# DESIGN7IH.net
KiCad netlist of a schematic drawn in EAGLE
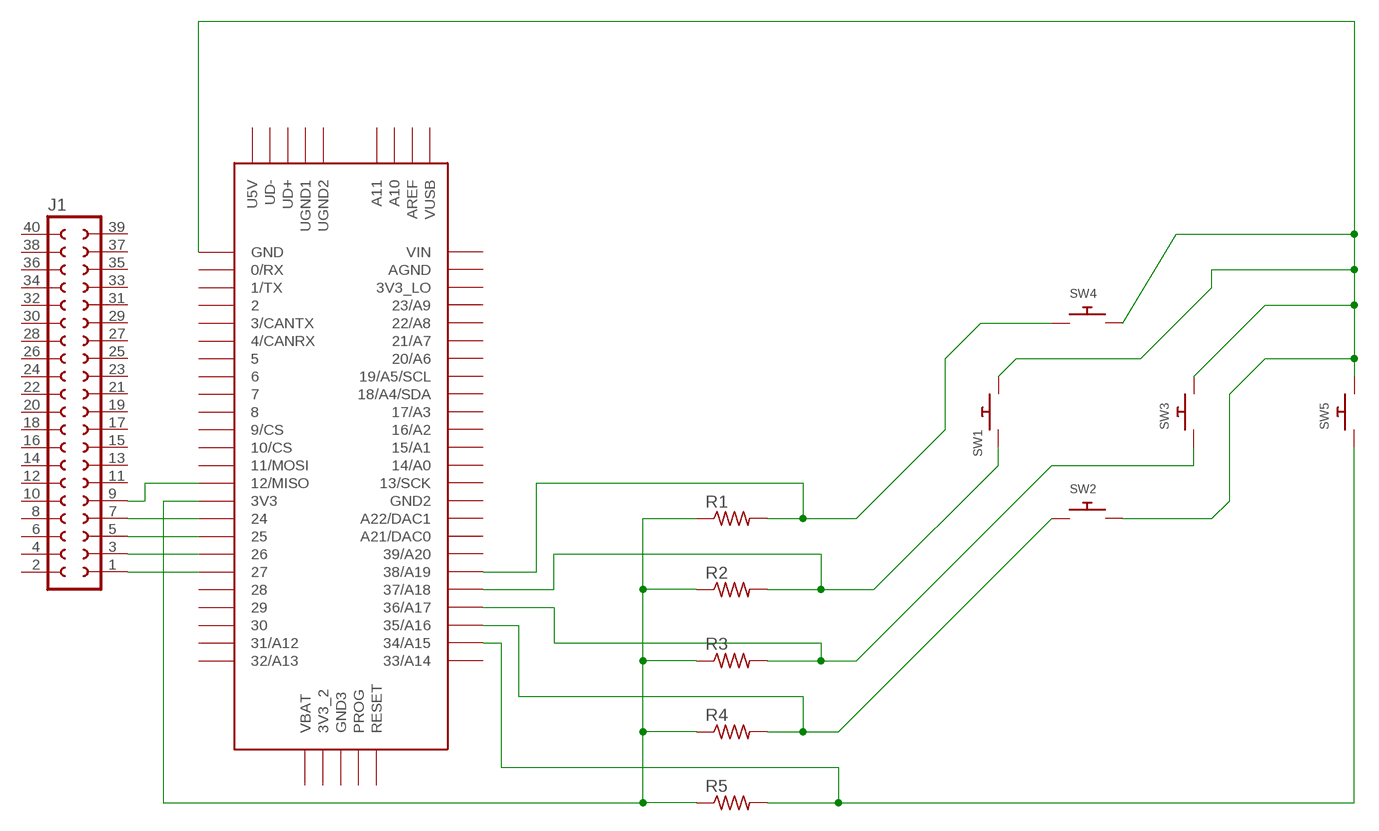
[diagram p0: schematic, sheet 1]

(export (version "E")
  (design (tool "Eeschema 10.0.6"))
  (components
    (comp (ref "J1")
      (value "SOCKET-40V")
      (footprint "eagle-import:S40V")
      (libsource (lib "eagle-import") (part "SOCKET-40V"))
    )
    (comp (ref "R1")
      (value "R-US_0204/5")
      (footprint "eagle-import:0204_5")
      (libsource (lib "eagle-import") (part "R-US_0204/5"))
    )
    (comp (ref "R2")
      (value "R-US_0204/5")
      (footprint "eagle-import:0204_5")
      (libsource (lib "eagle-import") (part "R-US_0204/5"))
    )
    (comp (ref "R3")
      (value "R-US_0204/5")
      (footprint "eagle-import:0204_5")
      (libsource (lib "eagle-import") (part "R-US_0204/5"))
    )
    (comp (ref "R4")
      (value "R-US_0204/5")
      (footprint "eagle-import:0204_5")
      (libsource (lib "eagle-import") (part "R-US_0204/5"))
    )
    (comp (ref "R5")
      (value "R-US_0204/5")
      (footprint "eagle-import:0204_5")
      (libsource (lib "eagle-import") (part "R-US_0204/5"))
    )
    (comp (ref "SW1")
      (value "SWITCH_PUSHBUTTONEVQ-PE")
      (footprint "eagle-import:TACT_PANA-EVQ")
      (libsource (lib "eagle-import") (part "SWITCH_PUSHBUTTONEVQ-PE"))
    )
    (comp (ref "SW2")
      (value "SWITCH_PUSHBUTTONEVQ-PE")
      (footprint "eagle-import:TACT_PANA-EVQ")
      (libsource (lib "eagle-import") (part "SWITCH_PUSHBUTTONEVQ-PE"))
    )
    (comp (ref "SW3")
      (value "SWITCH_PUSHBUTTONEVQ-PE")
      (footprint "eagle-import:TACT_PANA-EVQ")
      (libsource (lib "eagle-import") (part "SWITCH_PUSHBUTTONEVQ-PE"))
    )
    (comp (ref "SW4")
      (value "SWITCH_PUSHBUTTONEVQ-PE")
      (footprint "eagle-import:TACT_PANA-EVQ")
      (libsource (lib "eagle-import") (part "SWITCH_PUSHBUTTONEVQ-PE"))
    )
    (comp (ref "SW5")
      (value "SWITCH_PUSHBUTTONEVQ-PE")
      (footprint "eagle-import:TACT_PANA-EVQ")
      (libsource (lib "eagle-import") (part "SWITCH_PUSHBUTTONEVQ-PE"))
    )
    (comp (ref "U$1")
      (value "TEENSY_3.5/3.6")
      (footprint "eagle-import:TEENSY_3.5_3.6")
      (libsource (lib "eagle-import") (part "TEENSY_3.5/3.6"))
    )
  )
  (nets
    (net (code "1") (name "Net-(J1-Pad1)") (class "Default")
      (node (ref "J1") (pin "1") (pinfunction "1_1") (pintype "passive"))
      (node (ref "U$1") (pin "27") (pinfunction "27_27") (pintype "bidirectional"))
    )
    (net (code "2") (name "Net-(J1-Pad3)") (class "Default")
      (node (ref "J1") (pin "3") (pinfunction "3_3") (pintype "passive"))
      (node (ref "U$1") (pin "26") (pinfunction "26_26") (pintype "bidirectional"))
    )
    (net (code "3") (name "Net-(J1-Pad5)") (class "Default")
      (node (ref "J1") (pin "5") (pinfunction "5_5") (pintype "passive"))
      (node (ref "U$1") (pin "25") (pinfunction "25_25") (pintype "bidirectional"))
    )
    (net (code "4") (name "Net-(J1-Pad7)") (class "Default")
      (node (ref "J1") (pin "7") (pinfunction "7_7") (pintype "passive"))
      (node (ref "U$1") (pin "24") (pinfunction "24_24") (pintype "bidirectional"))
    )
    (net (code "5") (name "Net-(J1-Pad9)") (class "Default")
      (node (ref "J1") (pin "9") (pinfunction "9_9") (pintype "passive"))
      (node (ref "U$1") (pin "12/MISO") (pinfunction "12/MISO_12/MISO") (pintype "bidirectional"))
    )
    (net (code "6") (name "Net-(R1-Pad1)") (class "Default")
      (node (ref "R1") (pin "1") (pinfunction "1_1") (pintype "passive"))
      (node (ref "R2") (pin "1") (pinfunction "1_1") (pintype "passive"))
      (node (ref "R3") (pin "1") (pinfunction "1_1") (pintype "passive"))
      (node (ref "R4") (pin "1") (pinfunction "1_1") (pintype "passive"))
      (node (ref "R5") (pin "1") (pinfunction "1_1") (pintype "passive"))
      (node (ref "U$1") (pin "3V3") (pinfunction "3V3_3V3") (pintype "bidirectional"))
    )
    (net (code "7") (name "Net-(R1-Pad2)") (class "Default")
      (node (ref "R1") (pin "2") (pinfunction "2_2") (pintype "passive"))
      (node (ref "SW4") (pin "P$1") (pinfunction "P$1_P$1") (pintype "passive"))
      (node (ref "U$1") (pin "38/A19") (pinfunction "38/A19_38/A19") (pintype "bidirectional"))
    )
    (net (code "8") (name "Net-(R2-Pad2)") (class "Default")
      (node (ref "R2") (pin "2") (pinfunction "2_2") (pintype "passive"))
      (node (ref "SW1") (pin "P$1") (pinfunction "P$1_P$1") (pintype "passive"))
      (node (ref "U$1") (pin "37/A18") (pinfunction "37/A18_37/A18") (pintype "bidirectional"))
    )
    (net (code "9") (name "Net-(R3-Pad2)") (class "Default")
      (node (ref "R3") (pin "2") (pinfunction "2_2") (pintype "passive"))
      (node (ref "SW3") (pin "P$1") (pinfunction "P$1_P$1") (pintype "passive"))
      (node (ref "U$1") (pin "36/A17") (pinfunction "36/A17_36/A17") (pintype "bidirectional"))
    )
    (net (code "10") (name "Net-(R4-Pad2)") (class "Default")
      (node (ref "R4") (pin "2") (pinfunction "2_2") (pintype "passive"))
      (node (ref "SW2") (pin "P$1") (pinfunction "P$1_P$1") (pintype "passive"))
      (node (ref "U$1") (pin "35/A16") (pinfunction "35/A16_35/A16") (pintype "bidirectional"))
    )
    (net (code "11") (name "Net-(R5-Pad2)") (class "Default")
      (node (ref "R5") (pin "2") (pinfunction "2_2") (pintype "passive"))
      (node (ref "SW5") (pin "P$1") (pinfunction "P$1_P$1") (pintype "passive"))
      (node (ref "U$1") (pin "34/A15") (pinfunction "34/A15_34/A15") (pintype "bidirectional"))
    )
    (net (code "12") (name "Net-(SW1-PadP$2)") (class "Default")
      (node (ref "SW1") (pin "P$2") (pinfunction "P$2_P$2") (pintype "passive"))
      (node (ref "SW2") (pin "P$2") (pinfunction "P$2_P$2") (pintype "passive"))
      (node (ref "SW3") (pin "P$2") (pinfunction "P$2_P$2") (pintype "passive"))
      (node (ref "SW4") (pin "P$2") (pinfunction "P$2_P$2") (pintype "passive"))
      (node (ref "SW5") (pin "P$2") (pinfunction "P$2_P$2") (pintype "passive"))
      (node (ref "U$1") (pin "GND") (pinfunction "GND_GND") (pintype "bidirectional"))
    )
    (net (code "13") (name "unconnected-(J1-Pad2)") (class "Default")
      (node (ref "J1") (pin "2") (pinfunction "2_2") (pintype "passive"))
    )
    (net (code "14") (name "unconnected-(J1-Pad4)") (class "Default")
      (node (ref "J1") (pin "4") (pinfunction "4_4") (pintype "passive"))
    )
    (net (code "15") (name "unconnected-(J1-Pad6)") (class "Default")
      (node (ref "J1") (pin "6") (pinfunction "6_6") (pintype "passive"))
    )
    (net (code "16") (name "unconnected-(J1-Pad8)") (class "Default")
      (node (ref "J1") (pin "8") (pinfunction "8_8") (pintype "passive"))
    )
    (net (code "17") (name "unconnected-(J1-Pad10)") (class "Default")
      (node (ref "J1") (pin "10") (pinfunction "10_10") (pintype "passive"))
    )
    (net (code "18") (name "unconnected-(J1-Pad11)") (class "Default")
      (node (ref "J1") (pin "11") (pinfunction "11_11") (pintype "passive"))
    )
    (net (code "19") (name "unconnected-(J1-Pad12)") (class "Default")
      (node (ref "J1") (pin "12") (pinfunction "12_12") (pintype "passive"))
    )
    (net (code "20") (name "unconnected-(J1-Pad13)") (class "Default")
      (node (ref "J1") (pin "13") (pinfunction "13_13") (pintype "passive"))
    )
    (net (code "21") (name "unconnected-(J1-Pad14)") (class "Default")
      (node (ref "J1") (pin "14") (pinfunction "14_14") (pintype "passive"))
    )
    (net (code "22") (name "unconnected-(J1-Pad15)") (class "Default")
      (node (ref "J1") (pin "15") (pinfunction "15_15") (pintype "passive"))
    )
    (net (code "23") (name "unconnected-(J1-Pad16)") (class "Default")
      (node (ref "J1") (pin "16") (pinfunction "16_16") (pintype "passive"))
    )
    (net (code "24") (name "unconnected-(J1-Pad17)") (class "Default")
      (node (ref "J1") (pin "17") (pinfunction "17_17") (pintype "passive"))
    )
    (net (code "25") (name "unconnected-(J1-Pad18)") (class "Default")
      (node (ref "J1") (pin "18") (pinfunction "18_18") (pintype "passive"))
    )
    (net (code "26") (name "unconnected-(J1-Pad19)") (class "Default")
      (node (ref "J1") (pin "19") (pinfunction "19_19") (pintype "passive"))
    )
    (net (code "27") (name "unconnected-(J1-Pad20)") (class "Default")
      (node (ref "J1") (pin "20") (pinfunction "20_20") (pintype "passive"))
    )
    (net (code "28") (name "unconnected-(J1-Pad21)") (class "Default")
      (node (ref "J1") (pin "21") (pinfunction "21_21") (pintype "passive"))
    )
    (net (code "29") (name "unconnected-(J1-Pad22)") (class "Default")
      (node (ref "J1") (pin "22") (pinfunction "22_22") (pintype "passive"))
    )
    (net (code "30") (name "unconnected-(J1-Pad23)") (class "Default")
      (node (ref "J1") (pin "23") (pinfunction "23_23") (pintype "passive"))
    )
    (net (code "31") (name "unconnected-(J1-Pad24)") (class "Default")
      (node (ref "J1") (pin "24") (pinfunction "24_24") (pintype "passive"))
    )
    (net (code "32") (name "unconnected-(J1-Pad25)") (class "Default")
      (node (ref "J1") (pin "25") (pinfunction "25_25") (pintype "passive"))
    )
    (net (code "33") (name "unconnected-(J1-Pad26)") (class "Default")
      (node (ref "J1") (pin "26") (pinfunction "26_26") (pintype "passive"))
    )
    (net (code "34") (name "unconnected-(J1-Pad27)") (class "Default")
      (node (ref "J1") (pin "27") (pinfunction "27_27") (pintype "passive"))
    )
    (net (code "35") (name "unconnected-(J1-Pad28)") (class "Default")
      (node (ref "J1") (pin "28") (pinfunction "28_28") (pintype "passive"))
    )
    (net (code "36") (name "unconnected-(J1-Pad29)") (class "Default")
      (node (ref "J1") (pin "29") (pinfunction "29_29") (pintype "passive"))
    )
    (net (code "37") (name "unconnected-(J1-Pad30)") (class "Default")
      (node (ref "J1") (pin "30") (pinfunction "30_30") (pintype "passive"))
    )
    (net (code "38") (name "unconnected-(J1-Pad31)") (class "Default")
      (node (ref "J1") (pin "31") (pinfunction "31_31") (pintype "passive"))
    )
    (net (code "39") (name "unconnected-(J1-Pad32)") (class "Default")
      (node (ref "J1") (pin "32") (pinfunction "32_32") (pintype "passive"))
    )
    (net (code "40") (name "unconnected-(J1-Pad33)") (class "Default")
      (node (ref "J1") (pin "33") (pinfunction "33_33") (pintype "passive"))
    )
    (net (code "41") (name "unconnected-(J1-Pad34)") (class "Default")
      (node (ref "J1") (pin "34") (pinfunction "34_34") (pintype "passive"))
    )
    (net (code "42") (name "unconnected-(J1-Pad35)") (class "Default")
      (node (ref "J1") (pin "35") (pinfunction "35_35") (pintype "passive"))
    )
    (net (code "43") (name "unconnected-(J1-Pad36)") (class "Default")
      (node (ref "J1") (pin "36") (pinfunction "36_36") (pintype "passive"))
    )
    (net (code "44") (name "unconnected-(J1-Pad37)") (class "Default")
      (node (ref "J1") (pin "37") (pinfunction "37_37") (pintype "passive"))
    )
    (net (code "45") (name "unconnected-(J1-Pad38)") (class "Default")
      (node (ref "J1") (pin "38") (pinfunction "38_38") (pintype "passive"))
    )
    (net (code "46") (name "unconnected-(J1-Pad39)") (class "Default")
      (node (ref "J1") (pin "39") (pinfunction "39_39") (pintype "passive"))
    )
    (net (code "47") (name "unconnected-(J1-Pad40)") (class "Default")
      (node (ref "J1") (pin "40") (pinfunction "40_40") (pintype "passive"))
    )
    (net (code "48") (name "unconnected-(U$1-A21{slash}DAC0-Pad21{slash}DAC0)") (class "Default")
      (node (ref "U$1") (pin "21/DAC0") (pinfunction "A21/DAC0_21/DAC0") (pintype "bidirectional"))
    )
    (net (code "49") (name "unconnected-(U$1-Pad0{slash}RX)") (class "Default")
      (node (ref "U$1") (pin "0/RX") (pinfunction "0/RX_0/RX") (pintype "bidirectional"))
    )
    (net (code "50") (name "unconnected-(U$1-Pad1{slash}TX)") (class "Default")
      (node (ref "U$1") (pin "1/TX") (pinfunction "1/TX_1/TX") (pintype "bidirectional"))
    )
    (net (code "51") (name "unconnected-(U$1-Pad2)") (class "Default")
      (node (ref "U$1") (pin "2") (pinfunction "2_2") (pintype "bidirectional"))
    )
    (net (code "52") (name "unconnected-(U$1-Pad3V3_2)") (class "Default")
      (node (ref "U$1") (pin "3V3_2") (pinfunction "3V3_2_3V3_2") (pintype "bidirectional"))
    )
    (net (code "53") (name "unconnected-(U$1-Pad3V3_LO)") (class "Default")
      (node (ref "U$1") (pin "3V3_LO") (pinfunction "3V3_LO_3V3_LO") (pintype "bidirectional"))
    )
    (net (code "54") (name "unconnected-(U$1-Pad3{slash}CANTX)") (class "Default")
      (node (ref "U$1") (pin "3/CANTX") (pinfunction "3/CANTX_3/CANTX") (pintype "bidirectional"))
    )
    (net (code "55") (name "unconnected-(U$1-Pad4{slash}CANRX)") (class "Default")
      (node (ref "U$1") (pin "4/CANRX") (pinfunction "4/CANRX_4/CANRX") (pintype "bidirectional"))
    )
    (net (code "56") (name "unconnected-(U$1-Pad5)") (class "Default")
      (node (ref "U$1") (pin "5") (pinfunction "5_5") (pintype "bidirectional"))
    )
    (net (code "57") (name "unconnected-(U$1-Pad6)") (class "Default")
      (node (ref "U$1") (pin "6") (pinfunction "6_6") (pintype "bidirectional"))
    )
    (net (code "58") (name "unconnected-(U$1-Pad7)") (class "Default")
      (node (ref "U$1") (pin "7") (pinfunction "7_7") (pintype "bidirectional"))
    )
    (net (code "59") (name "unconnected-(U$1-Pad8)") (class "Default")
      (node (ref "U$1") (pin "8") (pinfunction "8_8") (pintype "bidirectional"))
    )
    (net (code "60") (name "unconnected-(U$1-Pad9{slash}CS)") (class "Default")
      (node (ref "U$1") (pin "9/CS") (pinfunction "9/CS_9/CS") (pintype "bidirectional"))
    )
    (net (code "61") (name "unconnected-(U$1-Pad10{slash}CS)") (class "Default")
      (node (ref "U$1") (pin "10/CS") (pinfunction "10/CS_10/CS") (pintype "bidirectional"))
    )
    (net (code "62") (name "unconnected-(U$1-Pad11{slash}MOSI)") (class "Default")
      (node (ref "U$1") (pin "11/MOSI") (pinfunction "11/MOSI_11/MOSI") (pintype "bidirectional"))
    )
    (net (code "63") (name "unconnected-(U$1-Pad13{slash}SCK)") (class "Default")
      (node (ref "U$1") (pin "13/SCK") (pinfunction "13/SCK_13/SCK") (pintype "bidirectional"))
    )
    (net (code "64") (name "unconnected-(U$1-Pad14{slash}A0)") (class "Default")
      (node (ref "U$1") (pin "14/A0") (pinfunction "14/A0_14/A0") (pintype "bidirectional"))
    )
    (net (code "65") (name "unconnected-(U$1-Pad15{slash}A1)") (class "Default")
      (node (ref "U$1") (pin "15/A1") (pinfunction "15/A1_15/A1") (pintype "bidirectional"))
    )
    (net (code "66") (name "unconnected-(U$1-Pad16{slash}A2)") (class "Default")
      (node (ref "U$1") (pin "16/A2") (pinfunction "16/A2_16/A2") (pintype "bidirectional"))
    )
    (net (code "67") (name "unconnected-(U$1-Pad17{slash}A3)") (class "Default")
      (node (ref "U$1") (pin "17/A3") (pinfunction "17/A3_17/A3") (pintype "bidirectional"))
    )
    (net (code "68") (name "unconnected-(U$1-Pad18{slash}A4{slash}SDA)") (class "Default")
      (node (ref "U$1") (pin "18/A4/SDA") (pinfunction "18/A4/SDA_18/A4/SDA") (pintype "bidirectional"))
    )
    (net (code "69") (name "unconnected-(U$1-Pad19{slash}A5{slash}SCL)") (class "Default")
      (node (ref "U$1") (pin "19/A5/SCL") (pinfunction "19/A5/SCL_19/A5/SCL") (pintype "bidirectional"))
    )
    (net (code "70") (name "unconnected-(U$1-Pad20{slash}A6)") (class "Default")
      (node (ref "U$1") (pin "20/A6") (pinfunction "20/A6_20/A6") (pintype "bidirectional"))
    )
    (net (code "71") (name "unconnected-(U$1-Pad21{slash}A7)") (class "Default")
      (node (ref "U$1") (pin "21/A7") (pinfunction "21/A7_21/A7") (pintype "bidirectional"))
    )
    (net (code "72") (name "unconnected-(U$1-Pad22{slash}A8)") (class "Default")
      (node (ref "U$1") (pin "22/A8") (pinfunction "22/A8_22/A8") (pintype "bidirectional"))
    )
    (net (code "73") (name "unconnected-(U$1-Pad23{slash}A9)") (class "Default")
      (node (ref "U$1") (pin "23/A9") (pinfunction "23/A9_23/A9") (pintype "bidirectional"))
    )
    (net (code "74") (name "unconnected-(U$1-Pad28)") (class "Default")
      (node (ref "U$1") (pin "28") (pinfunction "28_28") (pintype "bidirectional"))
    )
    (net (code "75") (name "unconnected-(U$1-Pad29)") (class "Default")
      (node (ref "U$1") (pin "29") (pinfunction "29_29") (pintype "bidirectional"))
    )
    (net (code "76") (name "unconnected-(U$1-Pad30)") (class "Default")
      (node (ref "U$1") (pin "30") (pinfunction "30_30") (pintype "bidirectional"))
    )
    (net (code "77") (name "unconnected-(U$1-Pad31{slash}A12)") (class "Default")
      (node (ref "U$1") (pin "31/A12") (pinfunction "31/A12_31/A12") (pintype "bidirectional"))
    )
    (net (code "78") (name "unconnected-(U$1-Pad32{slash}A13)") (class "Default")
      (node (ref "U$1") (pin "32/A13") (pinfunction "32/A13_32/A13") (pintype "bidirectional"))
    )
    (net (code "79") (name "unconnected-(U$1-Pad33{slash}A14)") (class "Default")
      (node (ref "U$1") (pin "33/A14") (pinfunction "33/A14_33/A14") (pintype "bidirectional"))
    )
    (net (code "80") (name "unconnected-(U$1-Pad39{slash}A20)") (class "Default")
      (node (ref "U$1") (pin "39/A20") (pinfunction "39/A20_39/A20") (pintype "bidirectional"))
    )
    (net (code "81") (name "unconnected-(U$1-PadA10)") (class "Default")
      (node (ref "U$1") (pin "A10") (pinfunction "A10_A10") (pintype "bidirectional"))
    )
    (net (code "82") (name "unconnected-(U$1-PadA11)") (class "Default")
      (node (ref "U$1") (pin "A11") (pinfunction "A11_A11") (pintype "bidirectional"))
    )
    (net (code "83") (name "unconnected-(U$1-PadA22{slash}DAC1)") (class "Default")
      (node (ref "U$1") (pin "A22/DAC1") (pinfunction "A22/DAC1_A22/DAC1") (pintype "bidirectional"))
    )
    (net (code "84") (name "unconnected-(U$1-PadAGND)") (class "Default")
      (node (ref "U$1") (pin "AGND") (pinfunction "AGND_AGND") (pintype "bidirectional"))
    )
    (net (code "85") (name "unconnected-(U$1-PadAREF)") (class "Default")
      (node (ref "U$1") (pin "AREF") (pinfunction "AREF_AREF") (pintype "bidirectional"))
    )
    (net (code "86") (name "unconnected-(U$1-PadGND2)") (class "Default")
      (node (ref "U$1") (pin "GND2") (pinfunction "GND2_GND2") (pintype "bidirectional"))
    )
    (net (code "87") (name "unconnected-(U$1-PadGND3)") (class "Default")
      (node (ref "U$1") (pin "GND3") (pinfunction "GND3_GND3") (pintype "bidirectional"))
    )
    (net (code "88") (name "unconnected-(U$1-PadPROG)") (class "Default")
      (node (ref "U$1") (pin "PROG") (pinfunction "PROG_PROG") (pintype "bidirectional"))
    )
    (net (code "89") (name "unconnected-(U$1-PadRESET)") (class "Default")
      (node (ref "U$1") (pin "RESET") (pinfunction "RESET_RESET") (pintype "bidirectional"))
    )
    (net (code "90") (name "unconnected-(U$1-PadU5V)") (class "Default")
      (node (ref "U$1") (pin "U5V") (pinfunction "U5V_U5V") (pintype "bidirectional"))
    )
    (net (code "91") (name "unconnected-(U$1-PadUD+)") (class "Default")
      (node (ref "U$1") (pin "UD+") (pinfunction "UD+_UD+") (pintype "bidirectional"))
    )
    (net (code "92") (name "unconnected-(U$1-PadUD-)") (class "Default")
      (node (ref "U$1") (pin "UD-") (pinfunction "UD-_UD-") (pintype "bidirectional"))
    )
    (net (code "93") (name "unconnected-(U$1-PadUGND1)") (class "Default")
      (node (ref "U$1") (pin "UGND1") (pinfunction "UGND1_UGND1") (pintype "bidirectional"))
    )
    (net (code "94") (name "unconnected-(U$1-PadUGND2)") (class "Default")
      (node (ref "U$1") (pin "UGND2") (pinfunction "UGND2_UGND2") (pintype "bidirectional"))
    )
    (net (code "95") (name "unconnected-(U$1-PadVBAT)") (class "Default")
      (node (ref "U$1") (pin "VBAT") (pinfunction "VBAT_VBAT") (pintype "bidirectional"))
    )
    (net (code "96") (name "unconnected-(U$1-PadVIN)") (class "Default")
      (node (ref "U$1") (pin "VIN") (pinfunction "VIN_VIN") (pintype "bidirectional"))
    )
    (net (code "97") (name "unconnected-(U$1-PadVUSB)") (class "Default")
      (node (ref "U$1") (pin "VUSB") (pinfunction "VUSB_VUSB") (pintype "bidirectional"))
    )
  )
)
